# Sensor.net
KiCad netlist of a schematic drawn in Altium Designer
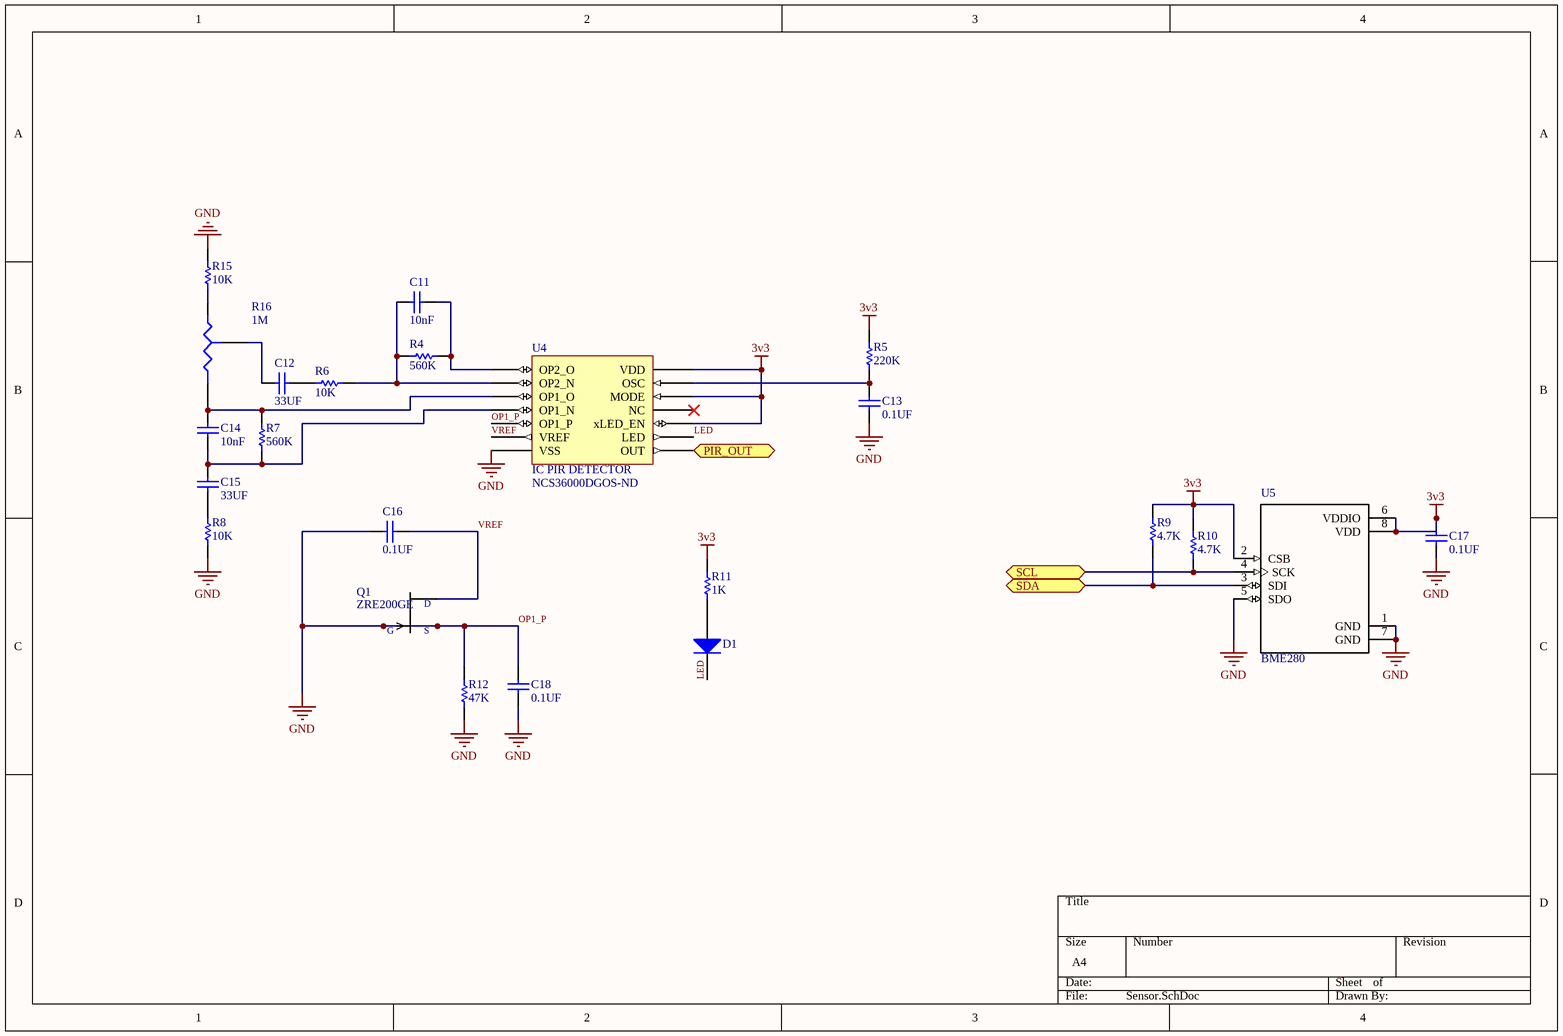
[diagram p0: Sensor.SchDoc]

(export (version "E")
  (design (tool "Eeschema 10.0.6"))
  (components
    (comp (ref "C11")
      (value "10nF")
      (footprint "Chip2PinSM127P600-8N-SAMSUNG-0603")
      (description "CAP CER 10000PF 50V X7R 0603")
      (fields
        (field (name "MANUFACTURER") "Samsung Electro-Mechanics")
        (field (name "MANUFACTURER PART NUMBER") "CL10B103KB8NCNC")
      )
      (libsource (lib "Schlib1") (part "CL10B103KB8NCNC"))
    )
    (comp (ref "C12")
      (value "33UF")
      (footprint "Chip2PinSM127P600-8N-TDK_0603")
      (description "CAP CER 33UF 6.3V X5R 0805")
      (fields
        (field (name "MANUFACTURER") "TDK Corporation")
        (field (name "MANUFACTURER PART NUMBER") "C2012X5R0J336M125AC")
      )
      (libsource (lib "Schlib1") (part "C2012X5R0J336M125AC"))
    )
    (comp (ref "C13")
      (value "0.1UF")
      (footprint "Chip2PinSM127P600-8N-SAMSUNG-0603")
      (description "CAP CER 0.1UF 16V Y5V 0603")
      (fields
        (field (name "MANUFACTURER") "Samsung Electro-Mechanics")
        (field (name "MANUFACTURER PART NUMBER") "CL10F104ZO8NNNC")
      )
      (libsource (lib "Schlib1") (part "CL10F104ZO8NNNC"))
    )
    (comp (ref "C14")
      (value "10nF")
      (footprint "Chip2PinSM127P600-8N-SAMSUNG-0603")
      (description "CAP CER 10000PF 50V X7R 0603")
      (fields
        (field (name "MANUFACTURER") "Samsung Electro-Mechanics")
        (field (name "MANUFACTURER PART NUMBER") "CL10B103KB8NCNC")
      )
      (libsource (lib "Schlib1") (part "CL10B103KB8NCNC"))
    )
    (comp (ref "C15")
      (value "33UF")
      (footprint "Chip2PinSM127P600-8N-TDK_0603")
      (description "CAP CER 33UF 6.3V X5R 0805")
      (fields
        (field (name "MANUFACTURER") "TDK Corporation")
        (field (name "MANUFACTURER PART NUMBER") "C2012X5R0J336M125AC")
      )
      (libsource (lib "Schlib1") (part "C2012X5R0J336M125AC"))
    )
    (comp (ref "C16")
      (value "0.1UF")
      (footprint "Chip2PinSM127P600-8N-SAMSUNG-0603")
      (description "CAP CER 0.1UF 16V Y5V 0603")
      (fields
        (field (name "MANUFACTURER") "Samsung Electro-Mechanics")
        (field (name "MANUFACTURER PART NUMBER") "CL10F104ZO8NNNC")
      )
      (libsource (lib "Schlib1") (part "CL10F104ZO8NNNC"))
    )
    (comp (ref "C17")
      (value "0.1UF")
      (footprint "Chip2PinSM127P600-8N-SAMSUNG-0603")
      (description "CAP CER 0.1UF 16V Y5V 0603")
      (fields
        (field (name "MANUFACTURER") "Samsung Electro-Mechanics")
        (field (name "MANUFACTURER PART NUMBER") "CL10F104ZO8NNNC")
      )
      (libsource (lib "Schlib1") (part "CL10F104ZO8NNNC"))
    )
    (comp (ref "C18")
      (value "0.1UF")
      (footprint "Chip2PinSM127P600-8N-SAMSUNG-0603")
      (description "CAP CER 0.1UF 16V Y5V 0603")
      (fields
        (field (name "MANUFACTURER") "Samsung Electro-Mechanics")
        (field (name "MANUFACTURER PART NUMBER") "CL10F104ZO8NNNC")
      )
      (libsource (lib "Schlib1") (part "CL10F104ZO8NNNC"))
    )
    (comp (ref "D1")
      (value "SML-D12M8WT86")
      (footprint "LED_0603_ROHM")
      (description "LED GREEN DIFFUSED 0603 SMD")
      (fields (field (name "MANUFACTURER") "Rohm Semiconductor") (field (name "BASE PART NUMBER") "SML-D12"))
      (libsource (lib "Schlib1") (part "SML-D12M8WT86"))
    )
    (comp (ref "Q1")
      (value "ZRE200GE")
      (footprint "TO5")
      (description "Zmotion Pir Sensor Dual Element")
      (fields (field (name "DIGI-KEY_PART_NUMBER") "269-4955-ND") (field (name "MF") "Zilog"))
      (libsource (lib "ZRE200GE") (part "ZRE200GE"))
    )
    (comp (ref "R4")
      (value "560K")
      (footprint "Chip2PinSM127P600-8N-Stackpole-0603")
      (description "RES SMD 560K OHM 1% 1/10W 0603")
      (fields
        (field (name "MANUFACTURER") "Panasonic Electronic Components")
        (field (name "MANUFACTURER PART NUMBER") "ERJ-3EKF5603V")
      )
      (libsource (lib "Schlib1") (part "ERJ-3EKF5603V"))
    )
    (comp (ref "R5")
      (value "220K")
      (footprint "Chip2PinSM127P600-8N-vishay-0603")
      (description "RES SMD 220K OHM 1% 1/10W 0603")
      (fields
        (field (name "MANUFACTURER") "Vishay Dale")
        (field (name "MANUFACTURER PART NUMBER") "CRCW0603220KFKEAC")
      )
      (libsource (lib "Schlib1") (part "CRCW0603220KFKEAC"))
    )
    (comp (ref "R6")
      (value "10K")
      (footprint "Chip2PinSM127P600-8N-vishay-0603")
      (description "RES SMD 10K OHM 1% 1/8W 0603")
      (fields
        (field (name "MANUFACTURER") "Vishay Beyschlag")
        (field (name "MANUFACTURER PART NUMBER") "MCT06030C1002FP500")
      )
      (libsource (lib "Schlib1") (part "MCT06030C1002FP500"))
    )
    (comp (ref "R7")
      (value "560K")
      (footprint "Chip2PinSM127P600-8N-Stackpole-0603")
      (description "RES SMD 560K OHM 1% 1/10W 0603")
      (fields
        (field (name "MANUFACTURER") "Panasonic Electronic Components")
        (field (name "MANUFACTURER PART NUMBER") "ERJ-3EKF5603V")
      )
      (libsource (lib "Schlib1") (part "ERJ-3EKF5603V"))
    )
    (comp (ref "R8")
      (value "10K")
      (footprint "Chip2PinSM127P600-8N-vishay-0603")
      (description "RES SMD 10K OHM 1% 1/8W 0603")
      (fields
        (field (name "MANUFACTURER") "Vishay Beyschlag")
        (field (name "MANUFACTURER PART NUMBER") "MCT06030C1002FP500")
      )
      (libsource (lib "Schlib1") (part "MCT06030C1002FP500"))
    )
    (comp (ref "R9")
      (value "4.7K")
      (footprint "Chip2PinSM127P600-8N-vishay-0603")
      (description "RES SMD 4.7K OHM 5% 1/10W 0603")
      (fields
        (field (name "MANUFACTURER") "Vishay Dale")
        (field (name "MANUFACTURER PART NUMBER") "CRCW06034K70JNEAC")
      )
      (libsource (lib "Schlib1") (part "CRCW06034K70JNEAC"))
    )
    (comp (ref "R10")
      (value "4.7K")
      (footprint "Chip2PinSM127P600-8N-vishay-0603")
      (description "RES SMD 4.7K OHM 5% 1/10W 0603")
      (fields
        (field (name "MANUFACTURER") "Vishay Dale")
        (field (name "MANUFACTURER PART NUMBER") "CRCW06034K70JNEAC")
      )
      (libsource (lib "Schlib1") (part "CRCW06034K70JNEAC"))
    )
    (comp (ref "R11")
      (value "1K")
      (footprint "Chip2PinSM127P600-8N-vishay-0603")
      (description "RES SMD 1K OHM 1% 1/8W 0603")
      (fields
        (field (name "MANUFACTURER") "Vishay Beyschlag")
        (field (name "MANUFACTURER PART NUMBER") "MCT06030C1001FP500")
      )
      (libsource (lib "Schlib1") (part "MCT06030C1001FP500"))
    )
    (comp (ref "R12")
      (value "47K")
      (footprint "Chip2PinSM127P600-8N-0603-te")
      (description "CRGCQ 0603 47K 1%")
      (fields
        (field (name "MANUFACTURER") "TE Connectivity Passive Product")
        (field (name "MANUFACTURER PART NUMBER") "CRGCQ0603F47K")
      )
      (libsource (lib "Schlib1") (part "CRGCQ0603F47K"))
    )
    (comp (ref "R15")
      (value "10K")
      (footprint "Chip2PinSM127P600-8N-vishay-0603")
      (description "RES SMD 10K OHM 1% 1/8W 0603")
      (fields
        (field (name "MANUFACTURER") "Vishay Beyschlag")
        (field (name "MANUFACTURER PART NUMBER") "MCT06030C1002FP500")
      )
      (libsource (lib "Schlib1") (part "MCT06030C1002FP500"))
    )
    (comp (ref "R16")
      (value "1M")
      (footprint "PCBComponent_1 - duplicate1")
      (description "Tapped Resistor")
      (fields
        (field (name "MANUFACTURER") "Bourns Inc.")
        (field (name "MANUFACTURER PART NUMBER") "TC33X-2-105E")
        (field (name "PUBLISHER") "Altium Limited")
      )
      (libsource (lib "Miscellaneous Devices") (part "Res Tap"))
    )
    (comp (ref "U4")
      (value "IC PIR DETECTOR")
      (footprint "SOIC127P600-8N-PIRIC_NCS36000")
      (description "IC PIR DETECTOR CTLR 14SOIC")
      (fields
        (field (name "MANUFACTURER") "ON Semiconductor")
        (field (name "MANUFACTURER PART NUMBER") "NCS36000DG")
        (field (name "SUPPLIER PART NUMBER 1") "NCS36000DGOS-ND")
      )
      (libsource (lib "Schlib1") (part "NCS36000DG"))
    )
    (comp (ref "U5")
      (value "BME280")
      (footprint "PSON65P250X250X100-8N")
      (description "Integrated pressure, humidity and temperature sensor; 8-pin 2.5x2.5x0.93mm LGA")
      (fields (field (name "DIGI-KEY_PART_NUMBER") "828-1063-1-ND") (field (name "MF") "Bosch"))
      (libsource (lib "BME280") (part "BME280"))
    )
  )
  (nets
    (net (code "1") (name "/LED") (class "Default")
      (node (ref "D1") (pin "2") (pinfunction "K_2") (pintype "passive"))
      (node (ref "U4") (pin "9") (pinfunction "LED_9") (pintype "output"))
    )
    (net (code "2") (name "/OP1_P") (class "Default")
      (node (ref "C18") (pin "1") (pinfunction "1_1") (pintype "passive"))
      (node (ref "Q1") (pin "2") (pinfunction "S_2") (pintype "passive"))
      (node (ref "R12") (pin "2") (pinfunction "2_2") (pintype "passive"))
      (node (ref "U4") (pin "5") (pinfunction "OP1_P_5") (pintype "bidirectional"))
    )
    (net (code "3") (name "/PIR_OUT") (class "Default")
      (node (ref "U4") (pin "8") (pinfunction "OUT_8") (pintype "output"))
    )
    (net (code "4") (name "/SCL") (class "Default")
      (node (ref "R10") (pin "1") (pinfunction "1_1") (pintype "passive"))
      (node (ref "U5") (pin "4") (pinfunction "SCK_4") (pintype "input"))
    )
    (net (code "5") (name "/SDA") (class "Default")
      (node (ref "R9") (pin "1") (pinfunction "1_1") (pintype "passive"))
      (node (ref "U5") (pin "3") (pinfunction "SDI_3") (pintype "bidirectional"))
    )
    (net (code "6") (name "/VREF") (class "Default")
      (node (ref "C16") (pin "2") (pinfunction "2_2") (pintype "passive"))
      (node (ref "Q1") (pin "1") (pinfunction "D_1") (pintype "passive"))
      (node (ref "U4") (pin "6") (pinfunction "VREF_6") (pintype "output"))
    )
    (net (code "7") (name "3v3") (class "Default")
      (node (ref "C17") (pin "2") (pinfunction "2_2") (pintype "passive"))
      (node (ref "R10") (pin "2") (pinfunction "2_2") (pintype "passive"))
      (node (ref "R11") (pin "2") (pinfunction "2_2") (pintype "passive"))
      (node (ref "R5") (pin "2") (pinfunction "2_2") (pintype "passive"))
      (node (ref "R9") (pin "2") (pinfunction "2_2") (pintype "passive"))
      (node (ref "U4") (pin "10") (pinfunction "xLED_EN_10") (pintype "bidirectional"))
      (node (ref "U4") (pin "12") (pinfunction "MODE_12") (pintype "input"))
      (node (ref "U4") (pin "14") (pinfunction "VDD_14") (pintype "power_in"))
      (node (ref "U5") (pin "2") (pinfunction "CSB_2") (pintype "input"))
      (node (ref "U5") (pin "6") (pinfunction "VDDIO_6") (pintype "power_in"))
      (node (ref "U5") (pin "8") (pinfunction "VDD_8") (pintype "power_in"))
    )
    (net (code "8") (name "GND") (class "Default")
      (node (ref "C13") (pin "2") (pinfunction "2_2") (pintype "passive"))
      (node (ref "C16") (pin "1") (pinfunction "1_1") (pintype "passive"))
      (node (ref "C17") (pin "1") (pinfunction "1_1") (pintype "passive"))
      (node (ref "C18") (pin "2") (pinfunction "2_2") (pintype "passive"))
      (node (ref "Q1") (pin "3") (pinfunction "G_3") (pintype "passive"))
      (node (ref "R12") (pin "1") (pinfunction "1_1") (pintype "passive"))
      (node (ref "R15") (pin "1") (pinfunction "1_1") (pintype "passive"))
      (node (ref "R8") (pin "2") (pinfunction "2_2") (pintype "passive"))
      (node (ref "U4") (pin "7") (pinfunction "VSS_7") (pintype "power_in"))
      (node (ref "U5") (pin "1") (pinfunction "GND_1") (pintype "power_in"))
      (node (ref "U5") (pin "5") (pinfunction "SDO_5") (pintype "bidirectional"))
      (node (ref "U5") (pin "7") (pinfunction "GND_7") (pintype "power_in"))
    )
    (net (code "9") (name "Net-(C12-Pad2)") (class "Default")
      (node (ref "C12") (pin "2") (pinfunction "2_2") (pintype "passive"))
      (node (ref "R6") (pin "1") (pinfunction "1_1") (pintype "passive"))
    )
    (net (code "10") (name "Net-(C15-Pad1)") (class "Default")
      (node (ref "C15") (pin "1") (pinfunction "1_1") (pintype "passive"))
      (node (ref "R8") (pin "1") (pinfunction "1_1") (pintype "passive"))
    )
    (net (code "11") (name "Net-(D1-A)") (class "Default")
      (node (ref "D1") (pin "1") (pinfunction "A_1") (pintype "passive"))
      (node (ref "R11") (pin "1") (pinfunction "1_1") (pintype "passive"))
    )
    (net (code "12") (name "Net-(R16-A)") (class "Default")
      (node (ref "R15") (pin "2") (pinfunction "2_2") (pintype "passive"))
      (node (ref "R16") (pin "1") (pinfunction "A_1") (pintype "passive"))
    )
    (net (code "13") (name "Net-(R16-B)") (class "Default")
      (node (ref "C14") (pin "1") (pinfunction "1_1") (pintype "passive"))
      (node (ref "R16") (pin "2") (pinfunction "B_2") (pintype "passive"))
      (node (ref "R7") (pin "2") (pinfunction "2_2") (pintype "passive"))
      (node (ref "U4") (pin "3") (pinfunction "OP1_O_3") (pintype "bidirectional"))
    )
    (net (code "14") (name "Net-(R16-TAP)") (class "Default")
      (node (ref "C12") (pin "1") (pinfunction "1_1") (pintype "passive"))
      (node (ref "R16") (pin "3") (pinfunction "TAP_3") (pintype "passive"))
    )
    (net (code "15") (name "Net-(U4-OP1_N)") (class "Default")
      (node (ref "C14") (pin "2") (pinfunction "2_2") (pintype "passive"))
      (node (ref "C15") (pin "2") (pinfunction "2_2") (pintype "passive"))
      (node (ref "R7") (pin "1") (pinfunction "1_1") (pintype "passive"))
      (node (ref "U4") (pin "4") (pinfunction "OP1_N_4") (pintype "bidirectional"))
    )
    (net (code "16") (name "Net-(U4-OP2_N)") (class "Default")
      (node (ref "C11") (pin "1") (pinfunction "1_1") (pintype "passive"))
      (node (ref "R4") (pin "1") (pinfunction "1_1") (pintype "passive"))
      (node (ref "R6") (pin "2") (pinfunction "2_2") (pintype "passive"))
      (node (ref "U4") (pin "2") (pinfunction "OP2_N_2") (pintype "bidirectional"))
    )
    (net (code "17") (name "Net-(U4-OP2_O)") (class "Default")
      (node (ref "C11") (pin "2") (pinfunction "2_2") (pintype "passive"))
      (node (ref "R4") (pin "2") (pinfunction "2_2") (pintype "passive"))
      (node (ref "U4") (pin "1") (pinfunction "OP2_O_1") (pintype "bidirectional"))
    )
    (net (code "18") (name "Net-(U4-OSC)") (class "Default")
      (node (ref "C13") (pin "1") (pinfunction "1_1") (pintype "passive"))
      (node (ref "R5") (pin "1") (pinfunction "1_1") (pintype "passive"))
      (node (ref "U4") (pin "13") (pinfunction "OSC_13") (pintype "input"))
    )
    (net (code "19") (name "unconnected-(U4-NC-Pad11)") (class "Default")
      (node (ref "U4") (pin "11") (pinfunction "NC_11") (pintype "passive+no_connect"))
    )
  )
)
